# power.net
KiCad netlist of a schematic drawn in Altium Designer
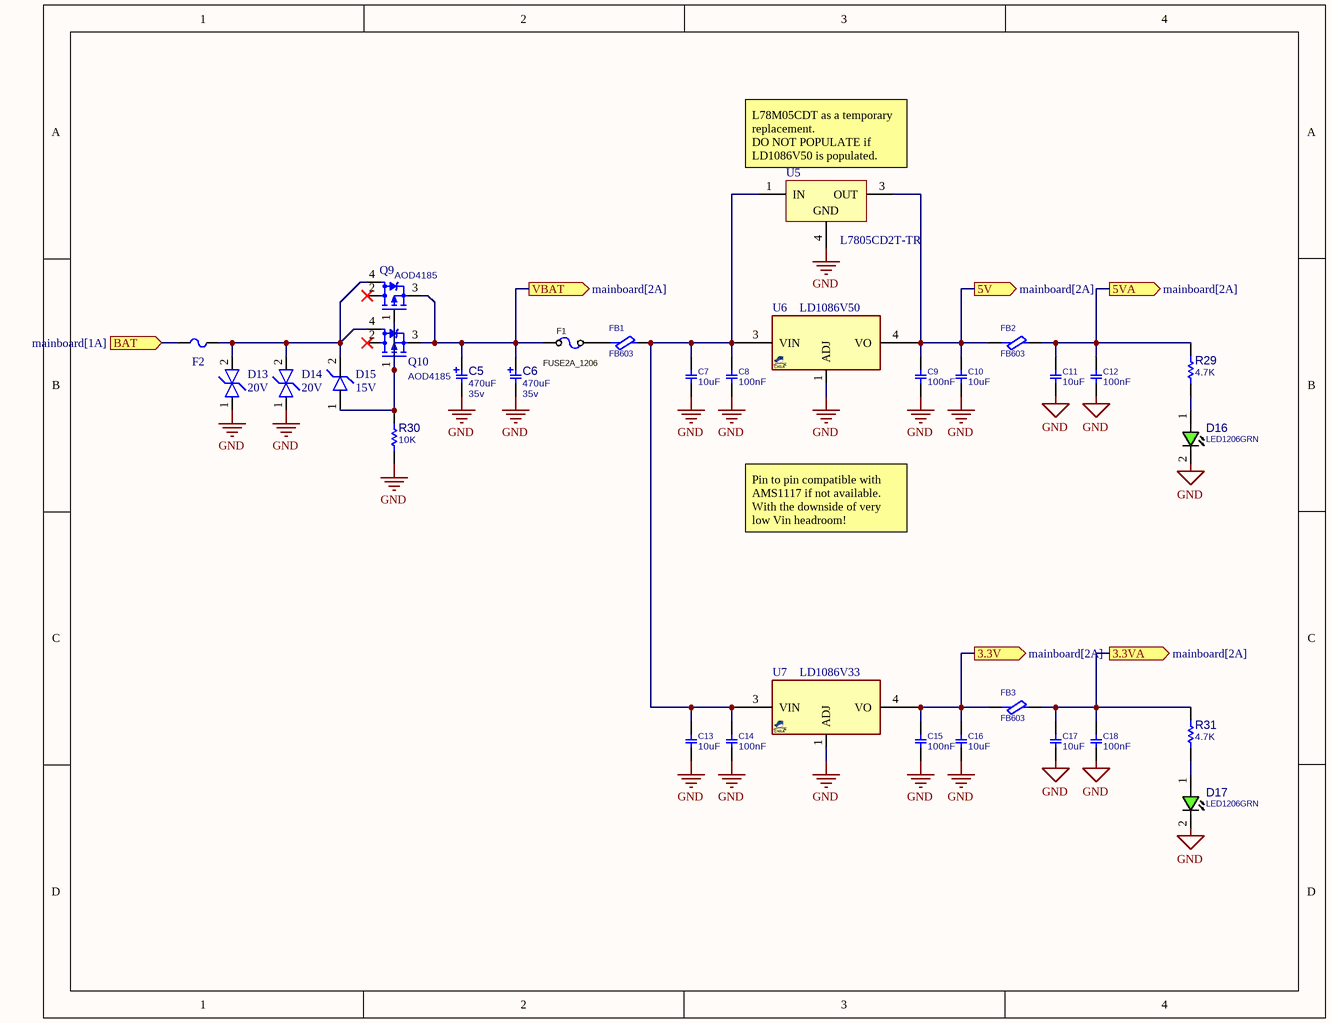
[diagram p0: power.SchDoc]

(export (version "E")
  (design (tool "Eeschema 10.0.6"))
  (components
    (comp (ref "C5")
      (value "470uF")
      (footprint "C_EL_D10L10")
      (description "CAP, SMD, ELEC,")
      (fields
        (field (name "MANF_P#") "MANF_PART#")
        (field (name "MANF") "MANF")
        (field (name "PARAM2") "35v")
      )
      (libsource (lib "passive_smd") (part "CAP_SMD_EL_470uF_35v"))
    )
    (comp (ref "C6")
      (value "470uF")
      (footprint "C_EL_D10L10")
      (description "CAP, SMD, ELEC,")
      (fields
        (field (name "MANF_P#") "MANF_PART#")
        (field (name "MANF") "MANF")
        (field (name "PARAM2") "35v")
      )
      (libsource (lib "passive_smd") (part "CAP_SMD_EL_470uF_35v"))
    )
    (comp (ref "C7")
      (value "10uF")
      (footprint "C1206")
      (description "CAP, MLCC")
      (fields (field (name "MANF_P#") "MANF_PART#") (field (name "MANF") "Murata"))
      (libsource (lib "passive_smd") (part "CAP_SMD_MLCC"))
    )
    (comp (ref "C8")
      (value "100nF")
      (footprint "C1206")
      (description "CAP, MLCC")
      (fields (field (name "MANF_P#") "MANF_PART#"))
      (libsource (lib "passive_smd") (part "CAP_SMD_MLCC_1206"))
    )
    (comp (ref "C9")
      (value "100nF")
      (footprint "C1206")
      (description "CAP, MLCC")
      (fields (field (name "MANF_P#") "MANF_PART#"))
      (libsource (lib "passive_smd") (part "CAP_SMD_MLCC_1206"))
    )
    (comp (ref "C10")
      (value "10uF")
      (footprint "C1206")
      (description "CAP, MLCC")
      (fields (field (name "MANF_P#") "MANF_PART#") (field (name "MANF") "Murata"))
      (libsource (lib "passive_smd") (part "CAP_SMD_MLCC"))
    )
    (comp (ref "C11")
      (value "10uF")
      (footprint "C1206")
      (description "CAP, MLCC")
      (fields (field (name "MANF_P#") "MANF_PART#") (field (name "MANF") "Murata"))
      (libsource (lib "passive_smd") (part "CAP_SMD_MLCC"))
    )
    (comp (ref "C12")
      (value "100nF")
      (footprint "C1206")
      (description "CAP, MLCC")
      (fields (field (name "MANF_P#") "MANF_PART#"))
      (libsource (lib "passive_smd") (part "CAP_SMD_MLCC_1206"))
    )
    (comp (ref "C13")
      (value "10uF")
      (footprint "C1206")
      (description "CAP, MLCC")
      (fields (field (name "MANF_P#") "MANF_PART#") (field (name "MANF") "Murata"))
      (libsource (lib "passive_smd") (part "CAP_SMD_MLCC"))
    )
    (comp (ref "C14")
      (value "100nF")
      (footprint "C1206")
      (description "CAP, MLCC")
      (fields (field (name "MANF_P#") "MANF_PART#"))
      (libsource (lib "passive_smd") (part "CAP_SMD_MLCC_1206"))
    )
    (comp (ref "C15")
      (value "100nF")
      (footprint "C1206")
      (description "CAP, MLCC")
      (fields (field (name "MANF_P#") "MANF_PART#"))
      (libsource (lib "passive_smd") (part "CAP_SMD_MLCC_1206"))
    )
    (comp (ref "C16")
      (value "10uF")
      (footprint "C1206")
      (description "CAP, MLCC")
      (fields (field (name "MANF_P#") "MANF_PART#") (field (name "MANF") "Murata"))
      (libsource (lib "passive_smd") (part "CAP_SMD_MLCC"))
    )
    (comp (ref "C17")
      (value "10uF")
      (footprint "C1206")
      (description "CAP, MLCC")
      (fields (field (name "MANF_P#") "MANF_PART#") (field (name "MANF") "Murata"))
      (libsource (lib "passive_smd") (part "CAP_SMD_MLCC"))
    )
    (comp (ref "C18")
      (value "100nF")
      (footprint "C1206")
      (description "CAP, MLCC")
      (fields (field (name "MANF_P#") "MANF_PART#"))
      (libsource (lib "passive_smd") (part "CAP_SMD_MLCC_1206"))
    )
    (comp (ref "D13")
      (value "20V")
      (footprint "FP-SMBJ-CA-MFG")
      (description "TVS DIODE")
      (libsource (lib "Alib") (part "TVS"))
    )
    (comp (ref "D14")
      (value "20V")
      (footprint "FP-SMBJ-CA-MFG")
      (description "TVS DIODE")
      (libsource (lib "Alib") (part "TVS"))
    )
    (comp (ref "D15") (value "15V") (footprint "D_SOD80") (libsource (lib "Alib") (part "Zener-SOD-80")))
    (comp (ref "D16")
      (value "LED1206GRN")
      (footprint "LED1206GRN")
      (description "LED, SMD, 1206, GREEN")
      (libsource (lib "led(diode)") (part "LED_SMD_1206_GRN"))
    )
    (comp (ref "D17")
      (value "LED1206GRN")
      (footprint "LED1206GRN")
      (description "LED, SMD, 1206, GREEN")
      (libsource (lib "led(diode)") (part "LED_SMD_1206_GRN"))
    )
    (comp (ref "F1")
      (value "FUSE2A_1206")
      (footprint "F1206")
      (description "Fuse, 3A, 32VDC, 1206, SMD, Slow Blow")
      (fields (field (name "MANF") "Bourns") (field (name "MANF_P#") "SF-1206SP300-2"))
      (libsource (lib "protect_tvs_esd_fuse") (part "FUSE_3A_1206_SLOW"))
    )
    (comp (ref "F2")
      (value "F=15 A")
      (footprint "FUSE - Double PAD")
      (description "Fuses 5x20")
      (fields (field (name "DESIGNER") "Abbas Basereh"))
      (libsource (lib "Alib") (part "Fuse 5x20 with holdeer pins"))
    )
    (comp (ref "FB1")
      (value "FB603")
      (footprint "L1206")
      (description "FERRITE_Bead, SMD")
      (fields (field (name "MANF") "MURATA") (field (name "MANF_P#") "BLM15AG121SN1D"))
      (libsource (lib "emi_filter") (part "FBEAD_SMD"))
    )
    (comp (ref "FB2")
      (value "FB603")
      (footprint "L1206")
      (description "FERRITE_Bead, SMD")
      (fields (field (name "MANF") "MURATA") (field (name "MANF_P#") "BLM15AG121SN1D"))
      (libsource (lib "emi_filter") (part "FBEAD_SMD"))
    )
    (comp (ref "FB3")
      (value "FB603")
      (footprint "L1206")
      (description "FERRITE_Bead, SMD")
      (fields (field (name "MANF") "MURATA") (field (name "MANF_P#") "BLM15AG121SN1D"))
      (libsource (lib "emi_filter") (part "FBEAD_SMD"))
    )
    (comp (ref "Q9")
      (value "AOD4185")
      (footprint "D2PAK_3")
      (description "HEXFET Power MOSFET")
      (fields (field (name "MANF_P#") "IRF4905"))
      (libsource (lib "transistor_fet") (part "MOSP_IRF4905_D2PAK"))
    )
    (comp (ref "Q10")
      (value "AOD4185")
      (footprint "D2PAK_3")
      (description "HEXFET Power MOSFET")
      (fields (field (name "MANF_P#") "IRF4905"))
      (libsource (lib "transistor_fet") (part "MOSP_IRF4905_D2PAK"))
    )
    (comp (ref "R29")
      (value "4.7K")
      (footprint "R0805")
      (description "RESISTOR, SMD")
      (libsource (lib "passive_smd") (part "RES_SMD_0805"))
    )
    (comp (ref "R30")
      (value "10K")
      (footprint "R0805")
      (description "RESISTOR, SMD")
      (libsource (lib "passive_smd") (part "RES_SMD_0805"))
    )
    (comp (ref "R31")
      (value "4.7K")
      (footprint "R0805")
      (description "RESISTOR, SMD")
      (libsource (lib "passive_smd") (part "RES_SMD_0805"))
    )
    (comp (ref "U5")
      (value "L7805CD2T-TR")
      (footprint "TO-263_M")
      (description "Positive Voltage Regulator, 3-Pin D2PAK, Tape and Reel")
      (libsource (lib "Altium Content Vault") (part "PM-REG-L4940-SOT3"))
    )
    (comp (ref "U6")
      (value "LD1086V50")
      (footprint "DPAK_3")
      (description "REG, Linear, LDO1.3, Adj, 1A, TO-252")
      (fields (field (name "MANF_P#") "LD1086DTTR, LD1086D2MTR") (field (name "MANF") "ST"))
      (libsource (lib "pwr_reg_linear_108x") (part "VREG_1086_TO252"))
    )
    (comp (ref "U7")
      (value "LD1086V33")
      (footprint "DPAK_3")
      (description "REG, Linear, LDO1.3, Adj, 1A, TO-252")
      (fields (field (name "MANF_P#") "LD1086DTTR, LD1086D2MTR") (field (name "MANF") "ST"))
      (libsource (lib "pwr_reg_linear_108x") (part "VREG_1086_TO252"))
    )
  )
  (nets
    (net (code "1") (name "/3.3V") (class "Default")
      (node (ref "C15") (pin "2") (pinfunction "2_2") (pintype "passive"))
      (node (ref "C16") (pin "2") (pinfunction "2_2") (pintype "passive"))
      (node (ref "FB3") (pin "2") (pinfunction "2_2") (pintype "passive"))
      (node (ref "U7") (pin "4") (pinfunction "VO_4") (pintype "passive"))
    )
    (net (code "2") (name "/3.3VA") (class "Default")
      (node (ref "C17") (pin "2") (pinfunction "2_2") (pintype "passive"))
      (node (ref "C18") (pin "2") (pinfunction "2_2") (pintype "passive"))
      (node (ref "FB3") (pin "1") (pinfunction "1_1") (pintype "passive"))
      (node (ref "R31") (pin "2") (pinfunction "2_2") (pintype "passive"))
    )
    (net (code "3") (name "/5V") (class "Default")
      (node (ref "C10") (pin "2") (pinfunction "2_2") (pintype "passive"))
      (node (ref "C9") (pin "2") (pinfunction "2_2") (pintype "passive"))
      (node (ref "FB2") (pin "2") (pinfunction "2_2") (pintype "passive"))
      (node (ref "U5") (pin "3") (pinfunction "OUT_3") (pintype "passive"))
      (node (ref "U6") (pin "4") (pinfunction "VO_4") (pintype "passive"))
    )
    (net (code "4") (name "/5VA") (class "Default")
      (node (ref "C11") (pin "2") (pinfunction "2_2") (pintype "passive"))
      (node (ref "C12") (pin "2") (pinfunction "2_2") (pintype "passive"))
      (node (ref "FB2") (pin "1") (pinfunction "1_1") (pintype "passive"))
      (node (ref "R29") (pin "2") (pinfunction "2_2") (pintype "passive"))
    )
    (net (code "5") (name "/BAT") (class "Default")
      (node (ref "F2") (pin "1") (pinfunction "1_1") (pintype "passive"))
    )
    (net (code "6") (name "/VBAT") (class "Default")
      (node (ref "C5") (pin "1") (pinfunction "1_1") (pintype "passive"))
      (node (ref "C6") (pin "1") (pinfunction "1_1") (pintype "passive"))
      (node (ref "F1") (pin "1") (pinfunction "1_1") (pintype "passive"))
      (node (ref "Q10") (pin "3") (pinfunction "S_3") (pintype "passive"))
      (node (ref "Q9") (pin "3") (pinfunction "S_3") (pintype "passive"))
    )
    (net (code "7") (name "GND") (class "Default")
      (node (ref "C10") (pin "1") (pinfunction "1_1") (pintype "passive"))
      (node (ref "C11") (pin "1") (pinfunction "1_1") (pintype "passive"))
      (node (ref "C12") (pin "1") (pinfunction "1_1") (pintype "passive"))
      (node (ref "C13") (pin "1") (pinfunction "1_1") (pintype "passive"))
      (node (ref "C14") (pin "1") (pinfunction "1_1") (pintype "passive"))
      (node (ref "C15") (pin "1") (pinfunction "1_1") (pintype "passive"))
      (node (ref "C16") (pin "1") (pinfunction "1_1") (pintype "passive"))
      (node (ref "C17") (pin "1") (pinfunction "1_1") (pintype "passive"))
      (node (ref "C18") (pin "1") (pinfunction "1_1") (pintype "passive"))
      (node (ref "C5") (pin "2") (pinfunction "2_2") (pintype "passive"))
      (node (ref "C6") (pin "2") (pinfunction "2_2") (pintype "passive"))
      (node (ref "C7") (pin "1") (pinfunction "1_1") (pintype "passive"))
      (node (ref "C8") (pin "1") (pinfunction "1_1") (pintype "passive"))
      (node (ref "C9") (pin "1") (pinfunction "1_1") (pintype "passive"))
      (node (ref "D13") (pin "1") (pinfunction "1_1") (pintype "passive"))
      (node (ref "D14") (pin "1") (pinfunction "1_1") (pintype "passive"))
      (node (ref "D16") (pin "2") (pinfunction "CATHODE_2") (pintype "passive"))
      (node (ref "D17") (pin "2") (pinfunction "CATHODE_2") (pintype "passive"))
      (node (ref "R30") (pin "1") (pinfunction "1_1") (pintype "passive"))
      (node (ref "U5") (pin "4") (pinfunction "GND_4") (pintype "power_in"))
      (node (ref "U6") (pin "1") (pinfunction "ADJ_1") (pintype "passive"))
      (node (ref "U7") (pin "1") (pinfunction "ADJ_1") (pintype "passive"))
    )
    (net (code "8") (name "Net-(D13-Pad2)") (class "Default")
      (node (ref "D13") (pin "2") (pinfunction "2_2") (pintype "passive"))
      (node (ref "D14") (pin "2") (pinfunction "2_2") (pintype "passive"))
      (node (ref "D15") (pin "2") (pinfunction "2_2") (pintype "passive"))
      (node (ref "F2") (pin "2") (pinfunction "2_2") (pintype "passive"))
      (node (ref "Q10") (pin "4") (pinfunction "D_4") (pintype "passive"))
      (node (ref "Q9") (pin "4") (pinfunction "D_4") (pintype "passive"))
    )
    (net (code "9") (name "Net-(D16-ANODE)") (class "Default")
      (node (ref "D16") (pin "1") (pinfunction "ANODE_1") (pintype "passive"))
      (node (ref "R29") (pin "1") (pinfunction "1_1") (pintype "passive"))
    )
    (net (code "10") (name "Net-(D17-ANODE)") (class "Default")
      (node (ref "D17") (pin "1") (pinfunction "ANODE_1") (pintype "passive"))
      (node (ref "R31") (pin "1") (pinfunction "1_1") (pintype "passive"))
    )
    (net (code "11") (name "Net-(F1-Pad2)") (class "Default")
      (node (ref "F1") (pin "2") (pinfunction "2_2") (pintype "passive"))
      (node (ref "FB1") (pin "2") (pinfunction "2_2") (pintype "passive"))
    )
    (net (code "12") (name "Net-(Q10-G)") (class "Default")
      (node (ref "D15") (pin "1") (pinfunction "1_1") (pintype "passive"))
      (node (ref "Q10") (pin "1") (pinfunction "G_1") (pintype "passive"))
      (node (ref "Q9") (pin "1") (pinfunction "G_1") (pintype "passive"))
      (node (ref "R30") (pin "2") (pinfunction "2_2") (pintype "passive"))
    )
    (net (code "13") (name "Net-(U5-IN)") (class "Default")
      (node (ref "C13") (pin "2") (pinfunction "2_2") (pintype "passive"))
      (node (ref "C14") (pin "2") (pinfunction "2_2") (pintype "passive"))
      (node (ref "C7") (pin "2") (pinfunction "2_2") (pintype "passive"))
      (node (ref "C8") (pin "2") (pinfunction "2_2") (pintype "passive"))
      (node (ref "FB1") (pin "1") (pinfunction "1_1") (pintype "passive"))
      (node (ref "U5") (pin "1") (pinfunction "IN_1") (pintype "power_in"))
      (node (ref "U6") (pin "3") (pinfunction "VIN_3") (pintype "passive"))
      (node (ref "U7") (pin "3") (pinfunction "VIN_3") (pintype "passive"))
    )
    (net (code "14") (name "unconnected-(Q9-D-Pad2)") (class "Default")
      (node (ref "Q9") (pin "2") (pinfunction "D_2") (pintype "passive+no_connect"))
    )
    (net (code "15") (name "unconnected-(Q10-D-Pad2)") (class "Default")
      (node (ref "Q10") (pin "2") (pinfunction "D_2") (pintype "passive+no_connect"))
    )
  )
)
